# ArduinoShield.net
KiCad netlist of a schematic drawn in EAGLE
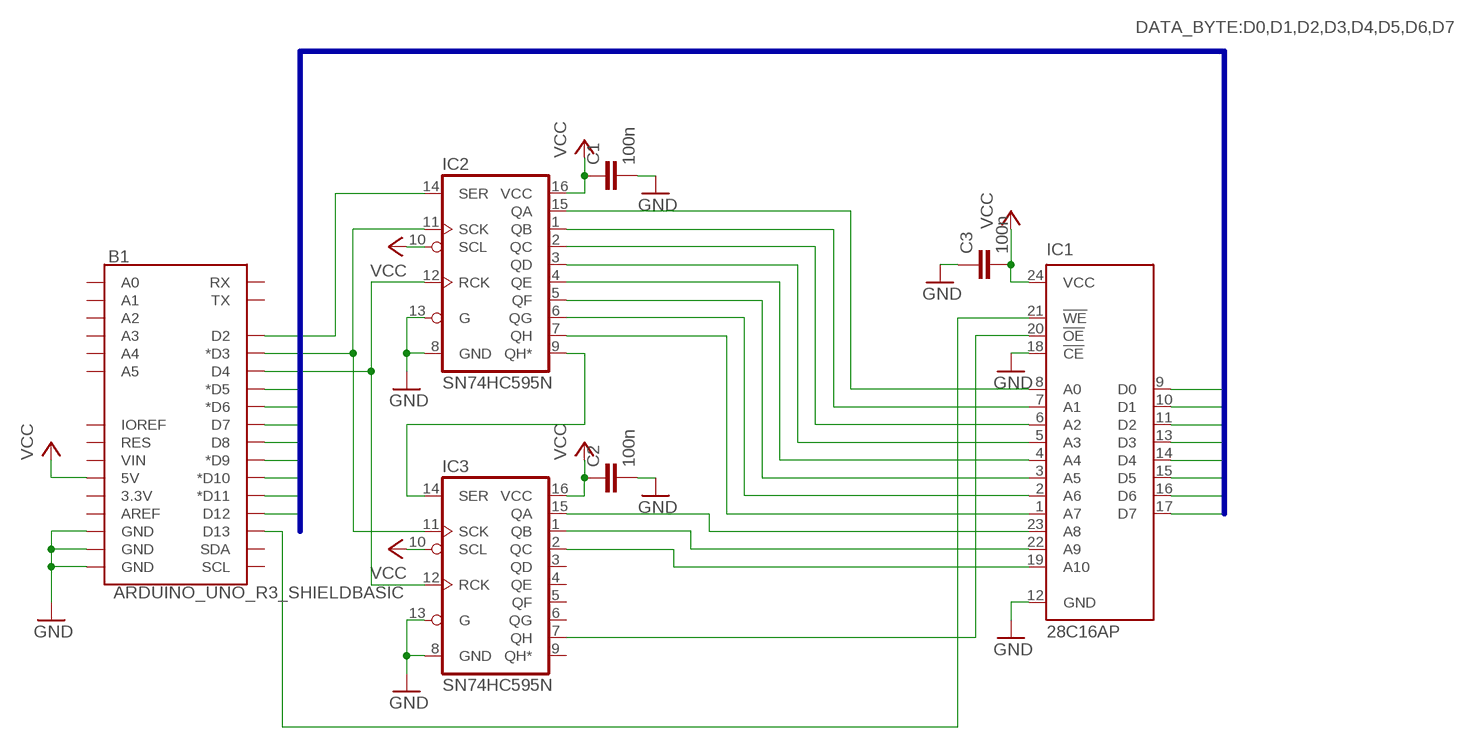
[diagram p0: schematic, sheet 1]

(export (version "E")
  (design (tool "Eeschema 10.0.6"))
  (components
    (comp (ref "B1")
      (value "ARDUINO_UNO_R3_SHIELDBASIC")
      (footprint "eagle-import:UNO_R3_SHIELD")
      (libsource (lib "eagle-import") (part "ARDUINO_UNO_R3_SHIELDBASIC"))
    )
    (comp (ref "C1")
      (value "100n")
      (footprint "eagle-import:C050-024X044")
      (libsource (lib "eagle-import") (part "C-EU050-024X044"))
    )
    (comp (ref "C2")
      (value "100n")
      (footprint "eagle-import:C050-024X044")
      (libsource (lib "eagle-import") (part "C-EU050-024X044"))
    )
    (comp (ref "C3")
      (value "100n")
      (footprint "eagle-import:C050-024X044")
      (libsource (lib "eagle-import") (part "C-EU050-024X044"))
    )
    (comp (ref "IC1")
      (value "28C16AP")
      (footprint "eagle-import:DIL24-6")
      (fields (field (name "MPN") "CAT28C16ALI-12"))
      (libsource (lib "eagle-import") (part "2816APC"))
    )
    (comp (ref "IC2")
      (value "SN74HC595N")
      (footprint "eagle-import:DIP16")
      (libsource (lib "eagle-import") (part "74595NHC"))
    )
    (comp (ref "IC3")
      (value "SN74HC595N")
      (footprint "eagle-import:DIP16")
      (libsource (lib "eagle-import") (part "74595NHC"))
    )
  )
  (nets
    (net (code "2") (name "/D0") (class "Default")
      (node (ref "B1") (pin "D5") (pinfunction "*D5_D5") (pintype "bidirectional"))
      (node (ref "IC1") (pin "9") (pinfunction "D0_9") (pintype "tri_state"))
    )
    (net (code "3") (name "/D1") (class "Default")
      (node (ref "B1") (pin "D6") (pinfunction "*D6_D6") (pintype "bidirectional"))
      (node (ref "IC1") (pin "10") (pinfunction "D1_10") (pintype "tri_state"))
    )
    (net (code "4") (name "/D2") (class "Default")
      (node (ref "B1") (pin "D7") (pinfunction "D7_D7") (pintype "bidirectional"))
      (node (ref "IC1") (pin "11") (pinfunction "D2_11") (pintype "tri_state"))
    )
    (net (code "5") (name "/D3") (class "Default")
      (node (ref "B1") (pin "D8") (pinfunction "D8_D8") (pintype "bidirectional"))
      (node (ref "IC1") (pin "13") (pinfunction "D3_13") (pintype "tri_state"))
    )
    (net (code "6") (name "/D4") (class "Default")
      (node (ref "B1") (pin "D9") (pinfunction "*D9_D9") (pintype "bidirectional"))
      (node (ref "IC1") (pin "14") (pinfunction "D4_14") (pintype "tri_state"))
    )
    (net (code "7") (name "/D5") (class "Default")
      (node (ref "B1") (pin "D10") (pinfunction "*D10_D10") (pintype "bidirectional"))
      (node (ref "IC1") (pin "15") (pinfunction "D5_15") (pintype "tri_state"))
    )
    (net (code "8") (name "/D6") (class "Default")
      (node (ref "B1") (pin "D11") (pinfunction "*D11_D11") (pintype "bidirectional"))
      (node (ref "IC1") (pin "16") (pinfunction "D6_16") (pintype "tri_state"))
    )
    (net (code "9") (name "/D7") (class "Default")
      (node (ref "B1") (pin "D12") (pinfunction "D12_D12") (pintype "bidirectional"))
      (node (ref "IC1") (pin "17") (pinfunction "D7_17") (pintype "tri_state"))
    )
    (net (code "11") (name "GND") (class "Default")
      (node (ref "B1") (pin "GND@0") (pinfunction "GND_GND@0") (pintype "bidirectional"))
      (node (ref "B1") (pin "GND@1") (pinfunction "GND_GND@1") (pintype "bidirectional"))
      (node (ref "B1") (pin "GND@2") (pinfunction "GND_GND@2") (pintype "bidirectional"))
      (node (ref "C1") (pin "2") (pinfunction "2_2") (pintype "passive"))
      (node (ref "C2") (pin "2") (pinfunction "2_2") (pintype "passive"))
      (node (ref "C3") (pin "1") (pinfunction "1_1") (pintype "passive"))
      (node (ref "IC1") (pin "12") (pinfunction "GND_12") (pintype "power_in"))
      (node (ref "IC1") (pin "18") (pinfunction "~{CE}_18") (pintype "input"))
      (node (ref "IC2") (pin "13") (pinfunction "G_13") (pintype "input"))
      (node (ref "IC2") (pin "8") (pinfunction "GND_8") (pintype "power_in"))
      (node (ref "IC3") (pin "13") (pinfunction "G_13") (pintype "input"))
      (node (ref "IC3") (pin "8") (pinfunction "GND_8") (pintype "power_in"))
    )
    (net (code "12") (name "Net-(B1-*D3)") (class "Default")
      (node (ref "B1") (pin "D3") (pinfunction "*D3_D3") (pintype "bidirectional"))
      (node (ref "IC2") (pin "11") (pinfunction "SCK_11") (pintype "input"))
      (node (ref "IC3") (pin "11") (pinfunction "SCK_11") (pintype "input"))
    )
    (net (code "13") (name "Net-(IC1-A0)") (class "Default")
      (node (ref "IC1") (pin "8") (pinfunction "A0_8") (pintype "input"))
      (node (ref "IC2") (pin "15") (pinfunction "QA_15") (pintype "tri_state"))
    )
    (net (code "14") (name "Net-(IC1-A1)") (class "Default")
      (node (ref "IC1") (pin "7") (pinfunction "A1_7") (pintype "input"))
      (node (ref "IC2") (pin "1") (pinfunction "QB_1") (pintype "tri_state"))
    )
    (net (code "15") (name "Net-(IC1-A2)") (class "Default")
      (node (ref "IC1") (pin "6") (pinfunction "A2_6") (pintype "input"))
      (node (ref "IC2") (pin "2") (pinfunction "QC_2") (pintype "tri_state"))
    )
    (net (code "16") (name "Net-(IC1-A3)") (class "Default")
      (node (ref "IC1") (pin "5") (pinfunction "A3_5") (pintype "input"))
      (node (ref "IC2") (pin "3") (pinfunction "QD_3") (pintype "tri_state"))
    )
    (net (code "17") (name "Net-(IC1-A4)") (class "Default")
      (node (ref "IC1") (pin "4") (pinfunction "A4_4") (pintype "input"))
      (node (ref "IC2") (pin "4") (pinfunction "QE_4") (pintype "tri_state"))
    )
    (net (code "18") (name "Net-(IC1-A5)") (class "Default")
      (node (ref "IC1") (pin "3") (pinfunction "A5_3") (pintype "input"))
      (node (ref "IC2") (pin "5") (pinfunction "QF_5") (pintype "tri_state"))
    )
    (net (code "19") (name "Net-(IC1-A6)") (class "Default")
      (node (ref "IC1") (pin "2") (pinfunction "A6_2") (pintype "input"))
      (node (ref "IC2") (pin "6") (pinfunction "QG_6") (pintype "tri_state"))
    )
    (net (code "20") (name "Net-(IC1-A7)") (class "Default")
      (node (ref "IC1") (pin "1") (pinfunction "A7_1") (pintype "input"))
      (node (ref "IC2") (pin "7") (pinfunction "QH_7") (pintype "tri_state"))
    )
    (net (code "21") (name "Net-(IC1-A8)") (class "Default")
      (node (ref "IC1") (pin "23") (pinfunction "A8_23") (pintype "input"))
      (node (ref "IC3") (pin "15") (pinfunction "QA_15") (pintype "tri_state"))
    )
    (net (code "22") (name "Net-(IC1-A9)") (class "Default")
      (node (ref "IC1") (pin "22") (pinfunction "A9_22") (pintype "input"))
      (node (ref "IC3") (pin "1") (pinfunction "QB_1") (pintype "tri_state"))
    )
    (net (code "23") (name "Net-(IC1-A10)") (class "Default")
      (node (ref "IC1") (pin "19") (pinfunction "A10_19") (pintype "input"))
      (node (ref "IC3") (pin "2") (pinfunction "QC_2") (pintype "tri_state"))
    )
    (net (code "24") (name "Net-(IC1-~{OE})") (class "Default")
      (node (ref "IC1") (pin "20") (pinfunction "~{OE}_20") (pintype "input"))
      (node (ref "IC3") (pin "7") (pinfunction "QH_7") (pintype "tri_state"))
    )
    (net (code "25") (name "Net-(IC1-~{WE})") (class "Default")
      (node (ref "B1") (pin "D13") (pinfunction "D13_D13") (pintype "bidirectional"))
      (node (ref "IC1") (pin "21") (pinfunction "~{WE}_21") (pintype "input"))
    )
    (net (code "26") (name "Net-(IC2-QH*)") (class "Default")
      (node (ref "IC2") (pin "9") (pinfunction "QH*_9") (pintype "tri_state"))
      (node (ref "IC3") (pin "14") (pinfunction "SER_14") (pintype "input"))
    )
    (net (code "27") (name "Net-(IC2-RCK)") (class "Default")
      (node (ref "B1") (pin "D4") (pinfunction "D4_D4") (pintype "bidirectional"))
      (node (ref "IC2") (pin "12") (pinfunction "RCK_12") (pintype "input"))
      (node (ref "IC3") (pin "12") (pinfunction "RCK_12") (pintype "input"))
    )
    (net (code "28") (name "Net-(IC2-SER)") (class "Default")
      (node (ref "B1") (pin "D2") (pinfunction "D2_D2") (pintype "bidirectional"))
      (node (ref "IC2") (pin "14") (pinfunction "SER_14") (pintype "input"))
    )
    (net (code "29") (name "VCC") (class "Default")
      (node (ref "B1") (pin "5V") (pinfunction "5V_5V") (pintype "bidirectional"))
      (node (ref "C1") (pin "1") (pinfunction "1_1") (pintype "passive"))
      (node (ref "C2") (pin "1") (pinfunction "1_1") (pintype "passive"))
      (node (ref "C3") (pin "2") (pinfunction "2_2") (pintype "passive"))
      (node (ref "IC1") (pin "24") (pinfunction "VCC_24") (pintype "power_in"))
      (node (ref "IC2") (pin "10") (pinfunction "SCL_10") (pintype "input"))
      (node (ref "IC2") (pin "16") (pinfunction "VCC_16") (pintype "power_in"))
      (node (ref "IC3") (pin "10") (pinfunction "SCL_10") (pintype "input"))
      (node (ref "IC3") (pin "16") (pinfunction "VCC_16") (pintype "power_in"))
    )
    (net (code "30") (name "unconnected-(B1-Pad3.3V)") (class "Default")
      (node (ref "B1") (pin "3.3V") (pinfunction "3.3V_3.3V") (pintype "bidirectional"))
    )
    (net (code "31") (name "unconnected-(B1-PadA0)") (class "Default")
      (node (ref "B1") (pin "A0") (pinfunction "A0_A0") (pintype "bidirectional"))
    )
    (net (code "32") (name "unconnected-(B1-PadA1)") (class "Default")
      (node (ref "B1") (pin "A1") (pinfunction "A1_A1") (pintype "bidirectional"))
    )
    (net (code "33") (name "unconnected-(B1-PadA2)") (class "Default")
      (node (ref "B1") (pin "A2") (pinfunction "A2_A2") (pintype "bidirectional"))
    )
    (net (code "34") (name "unconnected-(B1-PadA3)") (class "Default")
      (node (ref "B1") (pin "A3") (pinfunction "A3_A3") (pintype "bidirectional"))
    )
    (net (code "35") (name "unconnected-(B1-PadA4)") (class "Default")
      (node (ref "B1") (pin "A4") (pinfunction "A4_A4") (pintype "bidirectional"))
    )
    (net (code "36") (name "unconnected-(B1-PadA5)") (class "Default")
      (node (ref "B1") (pin "A5") (pinfunction "A5_A5") (pintype "bidirectional"))
    )
    (net (code "37") (name "unconnected-(B1-PadAREF)") (class "Default")
      (node (ref "B1") (pin "AREF") (pinfunction "AREF_AREF") (pintype "bidirectional"))
    )
    (net (code "38") (name "unconnected-(B1-PadIOREF)") (class "Default")
      (node (ref "B1") (pin "IOREF") (pinfunction "IOREF_IOREF") (pintype "bidirectional"))
    )
    (net (code "39") (name "unconnected-(B1-PadRES)") (class "Default")
      (node (ref "B1") (pin "RES") (pinfunction "RES_RES") (pintype "bidirectional"))
    )
    (net (code "40") (name "unconnected-(B1-PadRX)") (class "Default")
      (node (ref "B1") (pin "RX") (pinfunction "RX_RX") (pintype "bidirectional"))
    )
    (net (code "41") (name "unconnected-(B1-PadSCL)") (class "Default")
      (node (ref "B1") (pin "SCL") (pinfunction "SCL_SCL") (pintype "bidirectional"))
    )
    (net (code "42") (name "unconnected-(B1-PadSDA)") (class "Default")
      (node (ref "B1") (pin "SDA") (pinfunction "SDA_SDA") (pintype "bidirectional"))
    )
    (net (code "43") (name "unconnected-(B1-PadTX)") (class "Default")
      (node (ref "B1") (pin "TX") (pinfunction "TX_TX") (pintype "bidirectional"))
    )
    (net (code "44") (name "unconnected-(B1-PadVIN)") (class "Default")
      (node (ref "B1") (pin "VIN") (pinfunction "VIN_VIN") (pintype "bidirectional"))
    )
    (net (code "45") (name "unconnected-(IC3-QD-Pad3)") (class "Default")
      (node (ref "IC3") (pin "3") (pinfunction "QD_3") (pintype "tri_state"))
    )
    (net (code "46") (name "unconnected-(IC3-QE-Pad4)") (class "Default")
      (node (ref "IC3") (pin "4") (pinfunction "QE_4") (pintype "tri_state"))
    )
    (net (code "47") (name "unconnected-(IC3-QF-Pad5)") (class "Default")
      (node (ref "IC3") (pin "5") (pinfunction "QF_5") (pintype "tri_state"))
    )
    (net (code "48") (name "unconnected-(IC3-QG-Pad6)") (class "Default")
      (node (ref "IC3") (pin "6") (pinfunction "QG_6") (pintype "tri_state"))
    )
    (net (code "49") (name "unconnected-(IC3-QH*-Pad9)") (class "Default")
      (node (ref "IC3") (pin "9") (pinfunction "QH*_9") (pintype "tri_state"))
    )
  )
)
